# Driver.net
KiCad netlist of a schematic drawn in EAGLE
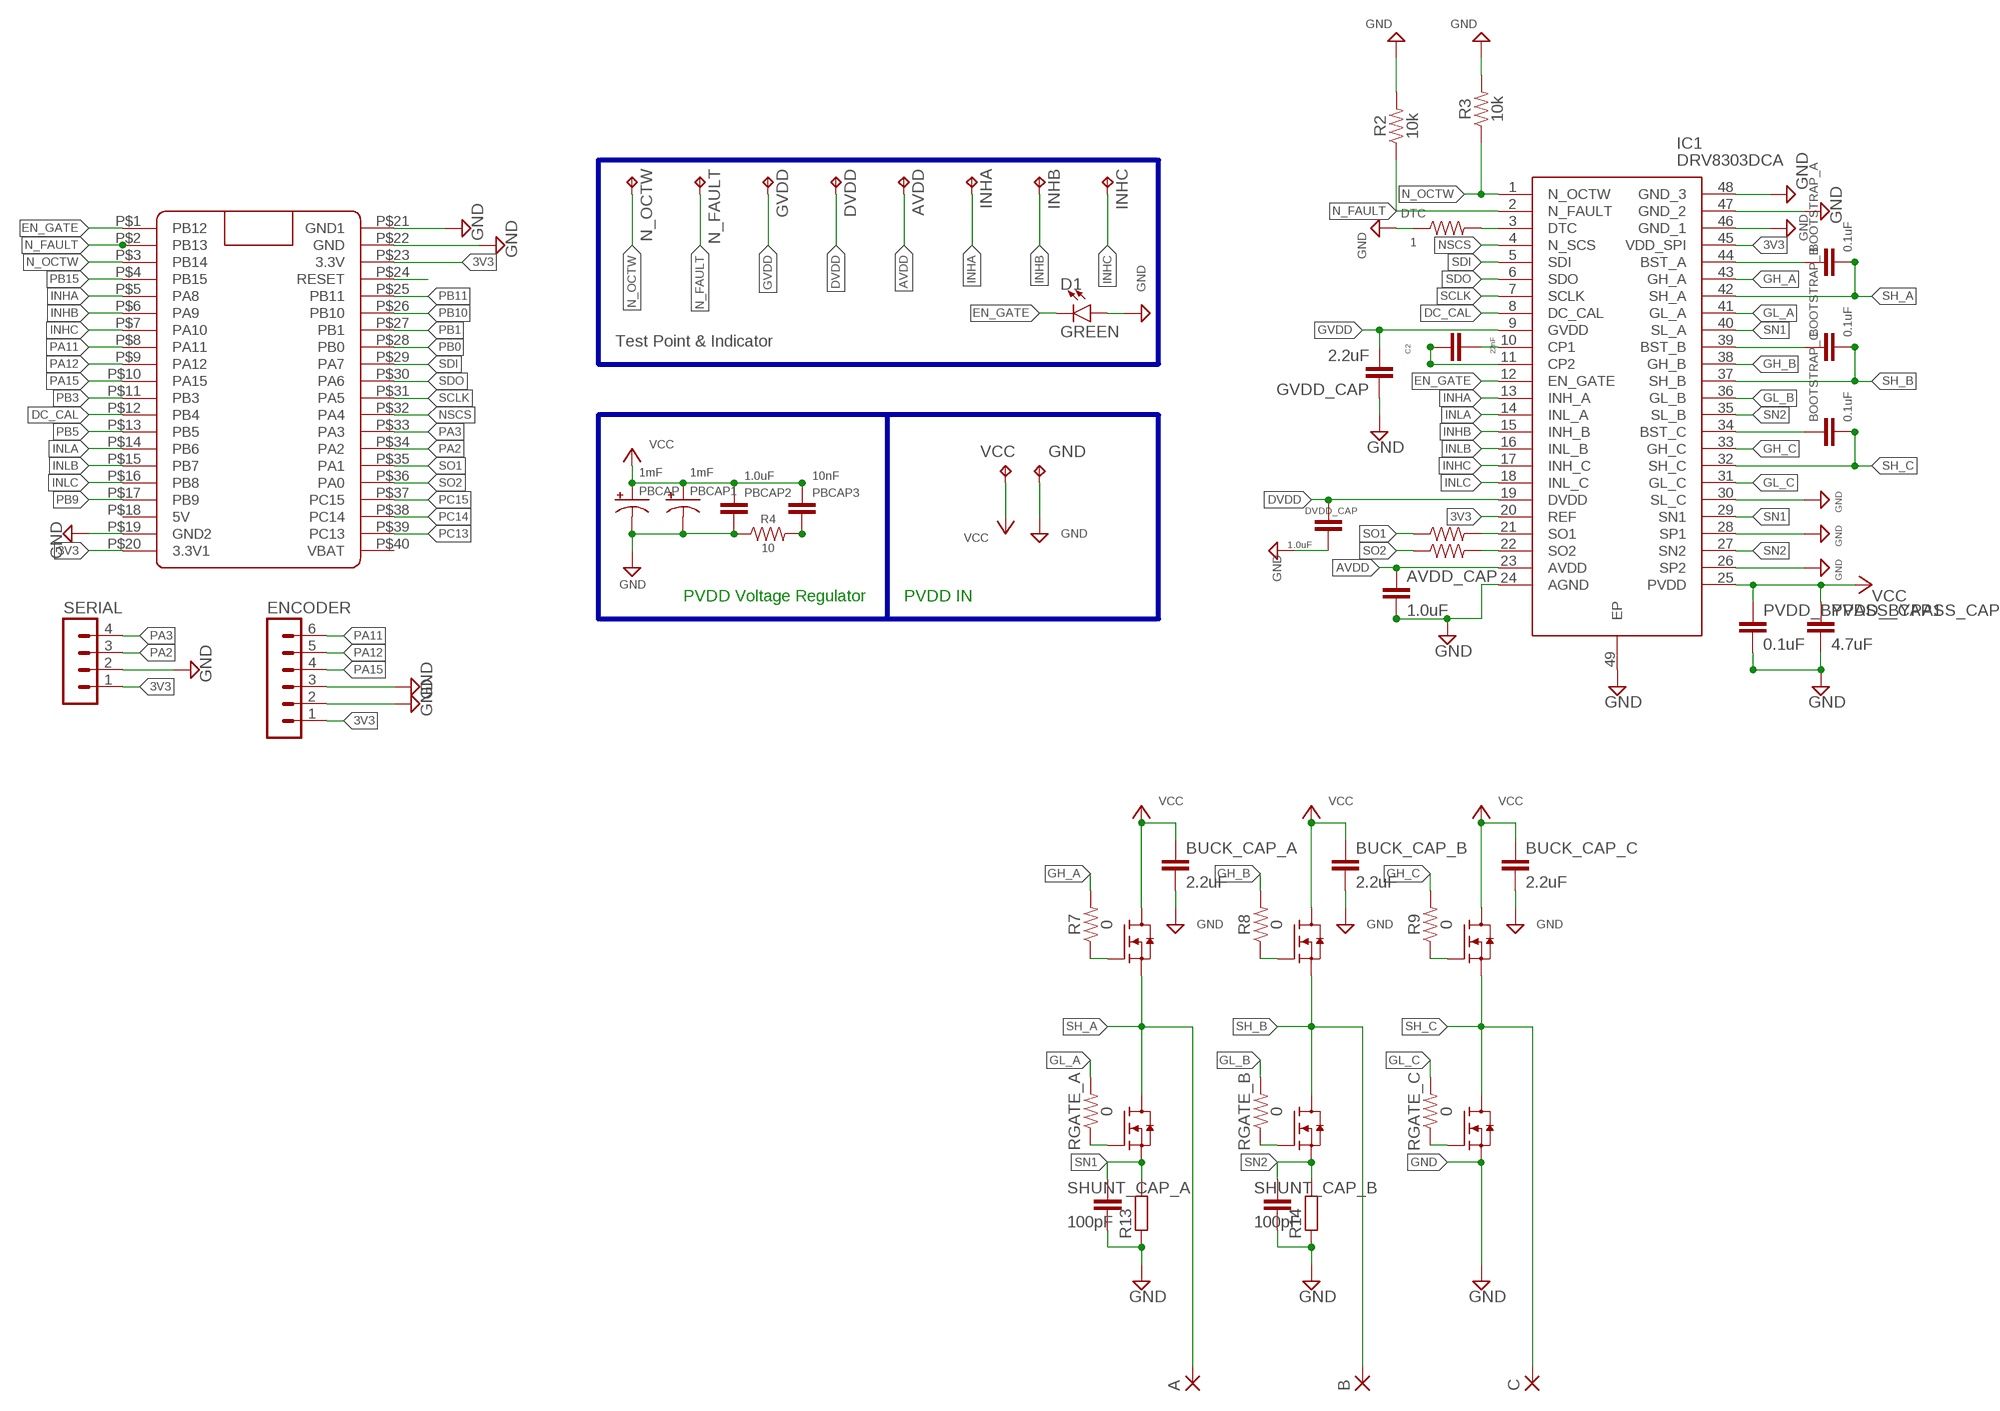
[diagram p0: schematic, sheet 1]

(export (version "E")
  (design (tool "Eeschema 10.0.6"))
  (components
    (comp (ref "A")
      (value "SMD5")
      (footprint "eagle-import:SMD2,54-5,08")
      (libsource (lib "eagle-import") (part "SMD5"))
    )
    (comp (ref "AVDD")
      (value "TPTP16R")
      (footprint "eagle-import:TP16R")
      (libsource (lib "eagle-import") (part "TPTP16R"))
    )
    (comp (ref "AVDD_CAP")
      (value "1.0uF")
      (footprint "eagle-import:0603")
      (libsource (lib "eagle-import") (part "1.0UF-0603-16V-10%"))
    )
    (comp (ref "B")
      (value "SMD5")
      (footprint "eagle-import:SMD2,54-5,08")
      (libsource (lib "eagle-import") (part "SMD5"))
    )
    (comp (ref "BOOTSTRAP_A")
      (value "0.1uF")
      (footprint "eagle-import:0603")
      (libsource (lib "eagle-import") (part "0.1UF-0603-25V-(+80/-20%)"))
    )
    (comp (ref "BOOTSTRAP_B")
      (value "0.1uF")
      (footprint "eagle-import:0603")
      (libsource (lib "eagle-import") (part "0.1UF-0603-25V-(+80/-20%)"))
    )
    (comp (ref "BOOTSTRAP_C")
      (value "0.1uF")
      (footprint "eagle-import:0603")
      (libsource (lib "eagle-import") (part "0.1UF-0603-25V-(+80/-20%)"))
    )
    (comp (ref "BUCK_CAP_A")
      (value "2.2uF")
      (footprint "eagle-import:0603")
      (libsource (lib "eagle-import") (part "2.2UF-0603-10V-20%"))
    )
    (comp (ref "BUCK_CAP_B")
      (value "2.2uF")
      (footprint "eagle-import:0603")
      (libsource (lib "eagle-import") (part "2.2UF-0603-10V-20%"))
    )
    (comp (ref "BUCK_CAP_C")
      (value "2.2uF")
      (footprint "eagle-import:0603")
      (libsource (lib "eagle-import") (part "2.2UF-0603-10V-20%"))
    )
    (comp (ref "C")
      (value "SMD5")
      (footprint "eagle-import:SMD2,54-5,08")
      (libsource (lib "eagle-import") (part "SMD5"))
    )
    (comp (ref "C2")
      (value "22nF")
      (footprint "eagle-import:0603")
      (libsource (lib "eagle-import") (part "22NF/22,000PF-0603-50V-10%"))
    )
    (comp (ref "D1")
      (value "GREEN")
      (footprint "eagle-import:LED-0603")
      (libsource (lib "eagle-import") (part "LED-GREEN0603"))
    )
    (comp (ref "DTC")
      (value "1")
      (footprint "eagle-import:0603")
      (libsource (lib "eagle-import") (part "1OHM-0603-1/10W-1%"))
    )
    (comp (ref "DVDD")
      (value "TPTP16R")
      (footprint "eagle-import:TP16R")
      (libsource (lib "eagle-import") (part "TPTP16R"))
    )
    (comp (ref "DVDD_CAP")
      (value "1.0uF")
      (footprint "eagle-import:0603")
      (libsource (lib "eagle-import") (part "1.0UF-0603-16V-10%"))
    )
    (comp (ref "ENCODER")
      (value "MA06-1")
      (footprint "eagle-import:MA06-1")
      (libsource (lib "eagle-import") (part "MA06-1"))
    )
    (comp (ref "GND")
      (value "TPPAD1-20Y")
      (footprint "eagle-import:P1-20Y")
      (libsource (lib "eagle-import") (part "TPPAD1-20Y"))
    )
    (comp (ref "GVDD")
      (value "TPTP16R")
      (footprint "eagle-import:TP16R")
      (libsource (lib "eagle-import") (part "TPTP16R"))
    )
    (comp (ref "GVDD_CAP")
      (value "2.2uF")
      (footprint "eagle-import:0603")
      (libsource (lib "eagle-import") (part "2.2UF-0603-10V-20%"))
    )
    (comp (ref "HA")
      (value "IRLR7843")
      (footprint "eagle-import:TO252")
      (libsource (lib "eagle-import") (part "IRLR7843"))
    )
    (comp (ref "HB")
      (value "IRLR7843")
      (footprint "eagle-import:TO252")
      (libsource (lib "eagle-import") (part "IRLR7843"))
    )
    (comp (ref "HC")
      (value "IRLR7843")
      (footprint "eagle-import:TO252")
      (libsource (lib "eagle-import") (part "IRLR7843"))
    )
    (comp (ref "IC1")
      (value "DRV8303DCA")
      (footprint "eagle-import:SOP50P810X120-49N")
      (fields (field (name "MOUSER_PART_NUMBER") "595-DRV8303DCA"))
      (libsource (lib "eagle-import") (part "DRV8303DCA"))
    )
    (comp (ref "INHA")
      (value "TPTP16R")
      (footprint "eagle-import:TP16R")
      (libsource (lib "eagle-import") (part "TPTP16R"))
    )
    (comp (ref "INHB")
      (value "TPTP16R")
      (footprint "eagle-import:TP16R")
      (libsource (lib "eagle-import") (part "TPTP16R"))
    )
    (comp (ref "INHC")
      (value "TPTP16R")
      (footprint "eagle-import:TP16R")
      (libsource (lib "eagle-import") (part "TPTP16R"))
    )
    (comp (ref "LA")
      (value "IRLR7843")
      (footprint "eagle-import:TO252")
      (libsource (lib "eagle-import") (part "IRLR7843"))
    )
    (comp (ref "LB")
      (value "IRLR7843")
      (footprint "eagle-import:TO252")
      (libsource (lib "eagle-import") (part "IRLR7843"))
    )
    (comp (ref "LC")
      (value "IRLR7843")
      (footprint "eagle-import:TO252")
      (libsource (lib "eagle-import") (part "IRLR7843"))
    )
    (comp (ref "N_FAULT")
      (value "TPTP16R")
      (footprint "eagle-import:TP16R")
      (libsource (lib "eagle-import") (part "TPTP16R"))
    )
    (comp (ref "N_OCTW")
      (value "TPTP16R")
      (footprint "eagle-import:TP16R")
      (libsource (lib "eagle-import") (part "TPTP16R"))
    )
    (comp (ref "PBCAP")
      (value "1mF")
      (footprint "eagle-import:CPOL-RADIAL-5MM-10MM")
      (libsource (lib "eagle-import") (part "1000UF-RADIAL-5MM-25V-20%"))
    )
    (comp (ref "PBCAP1")
      (value "1mF")
      (footprint "eagle-import:CPOL-RADIAL-5MM-10MM")
      (libsource (lib "eagle-import") (part "1000UF-RADIAL-5MM-25V-20%"))
    )
    (comp (ref "PBCAP2")
      (value "1.0uF")
      (footprint "eagle-import:0603")
      (libsource (lib "eagle-import") (part "1.0UF-0603-16V-10%"))
    )
    (comp (ref "PBCAP3")
      (value "10nF")
      (footprint "eagle-import:0603")
      (libsource (lib "eagle-import") (part "10NF-0603-50V-10%"))
    )
    (comp (ref "PVDD_BYPASS_CAP1")
      (value "0.1uF")
      (footprint "eagle-import:0603")
      (libsource (lib "eagle-import") (part "0.1UF-0603-25V-(+80/-20%)"))
    )
    (comp (ref "PVDD_BYPASS_CAP2")
      (value "4.7uF")
      (footprint "eagle-import:0603")
      (libsource (lib "eagle-import") (part "4.7UF-0603-35V-(20%)"))
    )
    (comp (ref "R2")
      (value "10k")
      (footprint "eagle-import:0603")
      (libsource (lib "eagle-import") (part "10KOHM-0603-1/10W-1%"))
    )
    (comp (ref "R3")
      (value "10k")
      (footprint "eagle-import:0603")
      (libsource (lib "eagle-import") (part "10KOHM-0603-1/10W-1%"))
    )
    (comp (ref "R4")
      (value "10")
      (footprint "eagle-import:0603")
      (libsource (lib "eagle-import") (part "10OHM-0603-1/10W-1%"))
    )
    (comp (ref "R5")
      (value "47")
      (footprint "eagle-import:0603")
      (libsource (lib "eagle-import") (part "47OHM-0603-1/10W-1%"))
    )
    (comp (ref "R6")
      (value "47")
      (footprint "eagle-import:0603")
      (libsource (lib "eagle-import") (part "47OHM-0603-1/10W-1%"))
    )
    (comp (ref "R7")
      (value "0")
      (footprint "eagle-import:0603")
      (libsource (lib "eagle-import") (part "0OHM-0603-1/10W"))
    )
    (comp (ref "R8")
      (value "0")
      (footprint "eagle-import:0603")
      (libsource (lib "eagle-import") (part "0OHM-0603-1/10W"))
    )
    (comp (ref "R9")
      (value "0")
      (footprint "eagle-import:0603")
      (libsource (lib "eagle-import") (part "0OHM-0603-1/10W"))
    )
    (comp (ref "R13")
      (value "R-EU_R2512")
      (footprint "eagle-import:R2512")
      (libsource (lib "eagle-import") (part "R-EU_R2512"))
    )
    (comp (ref "R14")
      (value "R-EU_R2512")
      (footprint "eagle-import:R2512")
      (libsource (lib "eagle-import") (part "R-EU_R2512"))
    )
    (comp (ref "RGATE_A")
      (value "0")
      (footprint "eagle-import:0603")
      (libsource (lib "eagle-import") (part "0OHM-0603-1/10W"))
    )
    (comp (ref "RGATE_B")
      (value "0")
      (footprint "eagle-import:0603")
      (libsource (lib "eagle-import") (part "0OHM-0603-1/10W"))
    )
    (comp (ref "RGATE_C")
      (value "0")
      (footprint "eagle-import:0603")
      (libsource (lib "eagle-import") (part "0OHM-0603-1/10W"))
    )
    (comp (ref "SERIAL")
      (value "MA04-1")
      (footprint "eagle-import:MA04-1")
      (libsource (lib "eagle-import") (part "MA04-1"))
    )
    (comp (ref "SHUNT_CAP_A")
      (value "100pF")
      (footprint "eagle-import:0603")
      (libsource (lib "eagle-import") (part "100PF-0603-50V-5%"))
    )
    (comp (ref "SHUNT_CAP_B")
      (value "100pF")
      (footprint "eagle-import:0603")
      (libsource (lib "eagle-import") (part "100PF-0603-50V-5%"))
    )
    (comp (ref "U$1")
      (value "BLUE_PILLADVANCED")
      (footprint "eagle-import:BLUE_PILL_ADV")
      (libsource (lib "eagle-import") (part "BLUE_PILLADVANCED"))
    )
    (comp (ref "VCC")
      (value "TPPAD1-20Y")
      (footprint "eagle-import:P1-20Y")
      (libsource (lib "eagle-import") (part "TPPAD1-20Y"))
    )
  )
  (nets
    (net (code "1") (name "3V3") (class "Default")
      (node (ref "ENCODER") (pin "1") (pinfunction "1_1") (pintype "passive"))
      (node (ref "IC1") (pin "20") (pinfunction "REF_20") (pintype "input"))
      (node (ref "IC1") (pin "45") (pinfunction "VDD_SPI_45") (pintype "power_in"))
      (node (ref "SERIAL") (pin "1") (pinfunction "1_1") (pintype "passive"))
      (node (ref "U$1") (pin "P$20") (pinfunction "3.3V1_P$20") (pintype "bidirectional"))
      (node (ref "U$1") (pin "P$23") (pinfunction "3.3V_P$23") (pintype "bidirectional"))
    )
    (net (code "2") (name "AVDD") (class "Default")
      (node (ref "AVDD") (pin "TP") (pinfunction "TP_TP") (pintype "input"))
      (node (ref "AVDD_CAP") (pin "1") (pinfunction "1_1") (pintype "passive"))
      (node (ref "IC1") (pin "23") (pinfunction "AVDD_23") (pintype "power_in"))
    )
    (net (code "3") (name "DC_CAL") (class "Default")
      (node (ref "IC1") (pin "8") (pinfunction "DC_CAL_8") (pintype "input"))
      (node (ref "U$1") (pin "P$12") (pinfunction "PB4_P$12") (pintype "bidirectional"))
    )
    (net (code "4") (name "DVDD") (class "Default")
      (node (ref "DVDD") (pin "TP") (pinfunction "TP_TP") (pintype "input"))
      (node (ref "DVDD_CAP") (pin "1") (pinfunction "1_1") (pintype "passive"))
      (node (ref "IC1") (pin "19") (pinfunction "DVDD_19") (pintype "power_in"))
    )
    (net (code "5") (name "EN_GATE") (class "Default")
      (node (ref "D1") (pin "C") (pinfunction "C_C") (pintype "passive"))
      (node (ref "IC1") (pin "12") (pinfunction "EN_GATE_12") (pintype "input"))
      (node (ref "U$1") (pin "P$1") (pinfunction "PB12_P$1") (pintype "bidirectional"))
    )
    (net (code "6") (name "GH_A") (class "Default")
      (node (ref "IC1") (pin "43") (pinfunction "GH_A_43") (pintype "output"))
      (node (ref "R7") (pin "2") (pinfunction "2_2") (pintype "passive"))
    )
    (net (code "7") (name "GH_B") (class "Default")
      (node (ref "IC1") (pin "38") (pinfunction "GH_B_38") (pintype "output"))
      (node (ref "R8") (pin "2") (pinfunction "2_2") (pintype "passive"))
    )
    (net (code "8") (name "GH_C") (class "Default")
      (node (ref "IC1") (pin "33") (pinfunction "GH_C_33") (pintype "output"))
      (node (ref "R9") (pin "2") (pinfunction "2_2") (pintype "passive"))
    )
    (net (code "9") (name "GL_A") (class "Default")
      (node (ref "IC1") (pin "41") (pinfunction "GL_A_41") (pintype "output"))
      (node (ref "RGATE_A") (pin "2") (pinfunction "2_2") (pintype "passive"))
    )
    (net (code "10") (name "GL_B") (class "Default")
      (node (ref "IC1") (pin "36") (pinfunction "GL_B_36") (pintype "output"))
      (node (ref "RGATE_B") (pin "2") (pinfunction "2_2") (pintype "passive"))
    )
    (net (code "11") (name "GL_C") (class "Default")
      (node (ref "IC1") (pin "31") (pinfunction "GL_C_31") (pintype "output"))
      (node (ref "RGATE_C") (pin "2") (pinfunction "2_2") (pintype "passive"))
    )
    (net (code "12") (name "GND") (class "Default")
      (node (ref "AVDD_CAP") (pin "2") (pinfunction "2_2") (pintype "passive"))
      (node (ref "BUCK_CAP_A") (pin "2") (pinfunction "2_2") (pintype "passive"))
      (node (ref "BUCK_CAP_B") (pin "2") (pinfunction "2_2") (pintype "passive"))
      (node (ref "BUCK_CAP_C") (pin "2") (pinfunction "2_2") (pintype "passive"))
      (node (ref "D1") (pin "A") (pinfunction "A_A") (pintype "passive"))
      (node (ref "DTC") (pin "1") (pinfunction "1_1") (pintype "passive"))
      (node (ref "DVDD_CAP") (pin "2") (pinfunction "2_2") (pintype "passive"))
      (node (ref "ENCODER") (pin "2") (pinfunction "2_2") (pintype "passive"))
      (node (ref "ENCODER") (pin "3") (pinfunction "3_3") (pintype "passive"))
      (node (ref "GND") (pin "TP") (pinfunction "TP_TP") (pintype "input"))
      (node (ref "GVDD_CAP") (pin "1") (pinfunction "1_1") (pintype "passive"))
      (node (ref "IC1") (pin "24") (pinfunction "AGND_24") (pintype "power_in"))
      (node (ref "IC1") (pin "26") (pinfunction "SP2_26") (pintype "input"))
      (node (ref "IC1") (pin "28") (pinfunction "SP1_28") (pintype "input"))
      (node (ref "IC1") (pin "30") (pinfunction "SL_C_30") (pintype "input"))
      (node (ref "IC1") (pin "46") (pinfunction "GND_1_46") (pintype "power_in"))
      (node (ref "IC1") (pin "47") (pinfunction "GND_2_47") (pintype "power_in"))
      (node (ref "IC1") (pin "48") (pinfunction "GND_3_48") (pintype "power_in"))
      (node (ref "IC1") (pin "49") (pinfunction "EP_49") (pintype "bidirectional"))
      (node (ref "LC") (pin "2") (pinfunction "S_2") (pintype "passive"))
      (node (ref "PBCAP") (pin "-") (pinfunction "-_-") (pintype "passive"))
      (node (ref "PBCAP1") (pin "-") (pinfunction "-_-") (pintype "passive"))
      (node (ref "PBCAP2") (pin "2") (pinfunction "2_2") (pintype "passive"))
      (node (ref "PVDD_BYPASS_CAP1") (pin "2") (pinfunction "2_2") (pintype "passive"))
      (node (ref "PVDD_BYPASS_CAP2") (pin "2") (pinfunction "2_2") (pintype "passive"))
      (node (ref "R13") (pin "1") (pinfunction "1_1") (pintype "passive"))
      (node (ref "R14") (pin "1") (pinfunction "1_1") (pintype "passive"))
      (node (ref "R2") (pin "2") (pinfunction "2_2") (pintype "passive"))
      (node (ref "R3") (pin "2") (pinfunction "2_2") (pintype "passive"))
      (node (ref "R4") (pin "1") (pinfunction "1_1") (pintype "passive"))
      (node (ref "SERIAL") (pin "2") (pinfunction "2_2") (pintype "passive"))
      (node (ref "SHUNT_CAP_A") (pin "2") (pinfunction "2_2") (pintype "passive"))
      (node (ref "SHUNT_CAP_B") (pin "2") (pinfunction "2_2") (pintype "passive"))
      (node (ref "U$1") (pin "P$19") (pinfunction "GND2_P$19") (pintype "bidirectional"))
      (node (ref "U$1") (pin "P$21") (pinfunction "GND1_P$21") (pintype "power_in"))
      (node (ref "U$1") (pin "P$22") (pinfunction "GND_P$22") (pintype "bidirectional"))
    )
    (net (code "13") (name "GVDD") (class "Default")
      (node (ref "GVDD") (pin "TP") (pinfunction "TP_TP") (pintype "input"))
      (node (ref "GVDD_CAP") (pin "2") (pinfunction "2_2") (pintype "passive"))
      (node (ref "IC1") (pin "9") (pinfunction "GVDD_9") (pintype "power_in"))
    )
    (net (code "14") (name "INHA") (class "Default")
      (node (ref "IC1") (pin "13") (pinfunction "INH_A_13") (pintype "input"))
      (node (ref "INHA") (pin "TP") (pinfunction "TP_TP") (pintype "input"))
      (node (ref "U$1") (pin "P$5") (pinfunction "PA8_P$5") (pintype "bidirectional"))
    )
    (net (code "15") (name "INHB") (class "Default")
      (node (ref "IC1") (pin "15") (pinfunction "INH_B_15") (pintype "input"))
      (node (ref "INHB") (pin "TP") (pinfunction "TP_TP") (pintype "input"))
      (node (ref "U$1") (pin "P$6") (pinfunction "PA9_P$6") (pintype "bidirectional"))
    )
    (net (code "16") (name "INHC") (class "Default")
      (node (ref "IC1") (pin "17") (pinfunction "INH_C_17") (pintype "input"))
      (node (ref "INHC") (pin "TP") (pinfunction "TP_TP") (pintype "input"))
      (node (ref "U$1") (pin "P$7") (pinfunction "PA10_P$7") (pintype "bidirectional"))
    )
    (net (code "17") (name "INLA") (class "Default")
      (node (ref "IC1") (pin "14") (pinfunction "INL_A_14") (pintype "input"))
      (node (ref "U$1") (pin "P$14") (pinfunction "PB6_P$14") (pintype "bidirectional"))
    )
    (net (code "18") (name "INLB") (class "Default")
      (node (ref "IC1") (pin "16") (pinfunction "INL_B_16") (pintype "input"))
      (node (ref "U$1") (pin "P$15") (pinfunction "PB7_P$15") (pintype "bidirectional"))
    )
    (net (code "19") (name "INLC") (class "Default")
      (node (ref "IC1") (pin "18") (pinfunction "INL_C_18") (pintype "input"))
      (node (ref "U$1") (pin "P$16") (pinfunction "PB8_P$16") (pintype "bidirectional"))
    )
    (net (code "20") (name "NSCS") (class "Default")
      (node (ref "IC1") (pin "4") (pinfunction "N_SCS_4") (pintype "input"))
      (node (ref "U$1") (pin "P$32") (pinfunction "PA4_P$32") (pintype "bidirectional"))
    )
    (net (code "21") (name "N_FAULT") (class "Default")
      (node (ref "IC1") (pin "2") (pinfunction "N_FAULT_2") (pintype "output"))
      (node (ref "N_FAULT") (pin "TP") (pinfunction "TP_TP") (pintype "input"))
      (node (ref "R2") (pin "1") (pinfunction "1_1") (pintype "passive"))
      (node (ref "U$1") (pin "P$2") (pinfunction "PB13_P$2") (pintype "bidirectional"))
    )
    (net (code "22") (name "N_OCTW") (class "Default")
      (node (ref "IC1") (pin "1") (pinfunction "N_OCTW_1") (pintype "output"))
      (node (ref "N_OCTW") (pin "TP") (pinfunction "TP_TP") (pintype "input"))
      (node (ref "R3") (pin "1") (pinfunction "1_1") (pintype "passive"))
      (node (ref "U$1") (pin "P$3") (pinfunction "PB14_P$3") (pintype "bidirectional"))
    )
    (net (code "23") (name "Net-(HA-G)") (class "Default")
      (node (ref "HA") (pin "1") (pinfunction "G_1") (pintype "passive"))
      (node (ref "R7") (pin "1") (pinfunction "1_1") (pintype "passive"))
    )
    (net (code "24") (name "Net-(HB-G)") (class "Default")
      (node (ref "HB") (pin "1") (pinfunction "G_1") (pintype "passive"))
      (node (ref "R8") (pin "1") (pinfunction "1_1") (pintype "passive"))
    )
    (net (code "25") (name "Net-(HC-G)") (class "Default")
      (node (ref "HC") (pin "1") (pinfunction "G_1") (pintype "passive"))
      (node (ref "R9") (pin "1") (pinfunction "1_1") (pintype "passive"))
    )
    (net (code "26") (name "Net-(IC1-BST_A)") (class "Default")
      (node (ref "BOOTSTRAP_A") (pin "1") (pinfunction "1_1") (pintype "passive"))
      (node (ref "IC1") (pin "44") (pinfunction "BST_A_44") (pintype "bidirectional"))
    )
    (net (code "27") (name "Net-(IC1-BST_B)") (class "Default")
      (node (ref "BOOTSTRAP_B") (pin "1") (pinfunction "1_1") (pintype "passive"))
      (node (ref "IC1") (pin "39") (pinfunction "BST_B_39") (pintype "bidirectional"))
    )
    (net (code "28") (name "Net-(IC1-BST_C)") (class "Default")
      (node (ref "BOOTSTRAP_C") (pin "1") (pinfunction "1_1") (pintype "passive"))
      (node (ref "IC1") (pin "34") (pinfunction "BST_C_34") (pintype "bidirectional"))
    )
    (net (code "29") (name "Net-(IC1-CP1)") (class "Default")
      (node (ref "C2") (pin "2") (pinfunction "2_2") (pintype "passive"))
      (node (ref "IC1") (pin "10") (pinfunction "CP1_10") (pintype "power_in"))
    )
    (net (code "30") (name "Net-(IC1-CP2)") (class "Default")
      (node (ref "C2") (pin "1") (pinfunction "1_1") (pintype "passive"))
      (node (ref "IC1") (pin "11") (pinfunction "CP2_11") (pintype "power_in"))
    )
    (net (code "31") (name "Net-(IC1-DTC)") (class "Default")
      (node (ref "DTC") (pin "2") (pinfunction "2_2") (pintype "passive"))
      (node (ref "IC1") (pin "3") (pinfunction "DTC_3") (pintype "input"))
    )
    (net (code "32") (name "Net-(IC1-SO1)") (class "Default")
      (node (ref "IC1") (pin "21") (pinfunction "SO1_21") (pintype "output"))
      (node (ref "R5") (pin "2") (pinfunction "2_2") (pintype "passive"))
    )
    (net (code "33") (name "Net-(IC1-SO2)") (class "Default")
      (node (ref "IC1") (pin "22") (pinfunction "SO2_22") (pintype "output"))
      (node (ref "R6") (pin "2") (pinfunction "2_2") (pintype "passive"))
    )
    (net (code "34") (name "Net-(LA-G)") (class "Default")
      (node (ref "LA") (pin "1") (pinfunction "G_1") (pintype "passive"))
      (node (ref "RGATE_A") (pin "1") (pinfunction "1_1") (pintype "passive"))
    )
    (net (code "35") (name "Net-(LB-G)") (class "Default")
      (node (ref "LB") (pin "1") (pinfunction "G_1") (pintype "passive"))
      (node (ref "RGATE_B") (pin "1") (pinfunction "1_1") (pintype "passive"))
    )
    (net (code "36") (name "Net-(LC-G)") (class "Default")
      (node (ref "LC") (pin "1") (pinfunction "G_1") (pintype "passive"))
      (node (ref "RGATE_C") (pin "1") (pinfunction "1_1") (pintype "passive"))
    )
    (net (code "37") (name "Net-(PBCAP3-Pad2)") (class "Default")
      (node (ref "PBCAP3") (pin "2") (pinfunction "2_2") (pintype "passive"))
      (node (ref "R4") (pin "2") (pinfunction "2_2") (pintype "passive"))
    )
    (net (code "38") (name "PA2") (class "Default")
      (node (ref "SERIAL") (pin "3") (pinfunction "3_3") (pintype "passive"))
      (node (ref "U$1") (pin "P$34") (pinfunction "PA2_P$34") (pintype "bidirectional"))
    )
    (net (code "39") (name "PA3") (class "Default")
      (node (ref "SERIAL") (pin "4") (pinfunction "4_4") (pintype "passive"))
      (node (ref "U$1") (pin "P$33") (pinfunction "PA3_P$33") (pintype "bidirectional"))
    )
    (net (code "40") (name "PA11") (class "Default")
      (node (ref "ENCODER") (pin "6") (pinfunction "6_6") (pintype "passive"))
      (node (ref "U$1") (pin "P$8") (pinfunction "PA11_P$8") (pintype "bidirectional"))
    )
    (net (code "41") (name "PA12") (class "Default")
      (node (ref "ENCODER") (pin "5") (pinfunction "5_5") (pintype "passive"))
      (node (ref "U$1") (pin "P$9") (pinfunction "PA12_P$9") (pintype "bidirectional"))
    )
    (net (code "42") (name "PA15") (class "Default")
      (node (ref "ENCODER") (pin "4") (pinfunction "4_4") (pintype "passive"))
      (node (ref "U$1") (pin "P$10") (pinfunction "PA15_P$10") (pintype "bidirectional"))
    )
    (net (code "43") (name "PB0") (class "Default")
      (node (ref "U$1") (pin "P$28") (pinfunction "PB0_P$28") (pintype "bidirectional"))
    )
    (net (code "44") (name "PB1") (class "Default")
      (node (ref "U$1") (pin "P$27") (pinfunction "PB1_P$27") (pintype "bidirectional"))
    )
    (net (code "45") (name "PB3") (class "Default")
      (node (ref "U$1") (pin "P$11") (pinfunction "PB3_P$11") (pintype "bidirectional"))
    )
    (net (code "46") (name "PB5") (class "Default")
      (node (ref "U$1") (pin "P$13") (pinfunction "PB5_P$13") (pintype "bidirectional"))
    )
    (net (code "47") (name "PB9") (class "Default")
      (node (ref "U$1") (pin "P$17") (pinfunction "PB9_P$17") (pintype "bidirectional"))
    )
    (net (code "48") (name "PB10") (class "Default")
      (node (ref "U$1") (pin "P$26") (pinfunction "PB10_P$26") (pintype "bidirectional"))
    )
    (net (code "49") (name "PB11") (class "Default")
      (node (ref "U$1") (pin "P$25") (pinfunction "PB11_P$25") (pintype "bidirectional"))
    )
    (net (code "50") (name "PB15") (class "Default")
      (node (ref "U$1") (pin "P$4") (pinfunction "PB15_P$4") (pintype "bidirectional"))
    )
    (net (code "51") (name "PC13") (class "Default")
      (node (ref "U$1") (pin "P$39") (pinfunction "PC13_P$39") (pintype "bidirectional"))
    )
    (net (code "52") (name "PC14") (class "Default")
      (node (ref "U$1") (pin "P$38") (pinfunction "PC14_P$38") (pintype "bidirectional"))
    )
    (net (code "53") (name "PC15") (class "Default")
      (node (ref "U$1") (pin "P$37") (pinfunction "PC15_P$37") (pintype "bidirectional"))
    )
    (net (code "54") (name "SCLK") (class "Default")
      (node (ref "IC1") (pin "7") (pinfunction "SCLK_7") (pintype "input"))
      (node (ref "U$1") (pin "P$31") (pinfunction "PA5_P$31") (pintype "bidirectional"))
    )
    (net (code "55") (name "SDI") (class "Default")
      (node (ref "IC1") (pin "5") (pinfunction "SDI_5") (pintype "input"))
      (node (ref "U$1") (pin "P$29") (pinfunction "PA7_P$29") (pintype "bidirectional"))
    )
    (net (code "56") (name "SDO") (class "Default")
      (node (ref "IC1") (pin "6") (pinfunction "SDO_6") (pintype "output"))
      (node (ref "U$1") (pin "P$30") (pinfunction "PA6_P$30") (pintype "bidirectional"))
    )
    (net (code "57") (name "SH_A") (class "Default")
      (node (ref "A") (pin "1") (pinfunction "P_1") (pintype "passive"))
      (node (ref "BOOTSTRAP_A") (pin "2") (pinfunction "2_2") (pintype "passive"))
      (node (ref "HA") (pin "2") (pinfunction "S_2") (pintype "passive"))
      (node (ref "IC1") (pin "42") (pinfunction "SH_A_42") (pintype "input"))
      (node (ref "LA") (pin "3") (pinfunction "D_3") (pintype "passive"))
    )
    (net (code "58") (name "SH_B") (class "Default")
      (node (ref "B") (pin "1") (pinfunction "P_1") (pintype "passive"))
      (node (ref "BOOTSTRAP_B") (pin "2") (pinfunction "2_2") (pintype "passive"))
      (node (ref "HB") (pin "2") (pinfunction "S_2") (pintype "passive"))
      (node (ref "IC1") (pin "37") (pinfunction "SH_B_37") (pintype "input"))
      (node (ref "LB") (pin "3") (pinfunction "D_3") (pintype "passive"))
    )
    (net (code "59") (name "SH_C") (class "Default")
      (node (ref "BOOTSTRAP_C") (pin "2") (pinfunction "2_2") (pintype "passive"))
      (node (ref "C") (pin "1") (pinfunction "P_1") (pintype "passive"))
      (node (ref "HC") (pin "2") (pinfunction "S_2") (pintype "passive"))
      (node (ref "IC1") (pin "32") (pinfunction "SH_C_32") (pintype "input"))
      (node (ref "LC") (pin "3") (pinfunction "D_3") (pintype "passive"))
    )
    (net (code "60") (name "SN1") (class "Default")
      (node (ref "IC1") (pin "29") (pinfunction "SN1_29") (pintype "input"))
      (node (ref "IC1") (pin "40") (pinfunction "SL_A_40") (pintype "input"))
      (node (ref "LA") (pin "2") (pinfunction "S_2") (pintype "passive"))
      (node (ref "R13") (pin "2") (pinfunction "2_2") (pintype "passive"))
      (node (ref "SHUNT_CAP_A") (pin "1") (pinfunction "1_1") (pintype "passive"))
    )
    (net (code "61") (name "SN2") (class "Default")
      (node (ref "IC1") (pin "27") (pinfunction "SN2_27") (pintype "input"))
      (node (ref "IC1") (pin "35") (pinfunction "SL_B_35") (pintype "input"))
      (node (ref "LB") (pin "2") (pinfunction "S_2") (pintype "passive"))
      (node (ref "R14") (pin "2") (pinfunction "2_2") (pintype "passive"))
      (node (ref "SHUNT_CAP_B") (pin "1") (pinfunction "1_1") (pintype "passive"))
    )
    (net (code "62") (name "SO1") (class "Default")
      (node (ref "R5") (pin "1") (pinfunction "1_1") (pintype "passive"))
      (node (ref "U$1") (pin "P$35") (pinfunction "PA1_P$35") (pintype "bidirectional"))
    )
    (net (code "63") (name "SO2") (class "Default")
      (node (ref "R6") (pin "1") (pinfunction "1_1") (pintype "passive"))
      (node (ref "U$1") (pin "P$36") (pinfunction "PA0_P$36") (pintype "bidirectional"))
    )
    (net (code "64") (name "VCC") (class "Default")
      (node (ref "BUCK_CAP_A") (pin "1") (pinfunction "1_1") (pintype "passive"))
      (node (ref "BUCK_CAP_B") (pin "1") (pinfunction "1_1") (pintype "passive"))
      (node (ref "BUCK_CAP_C") (pin "1") (pinfunction "1_1") (pintype "passive"))
      (node (ref "HA") (pin "3") (pinfunction "D_3") (pintype "passive"))
      (node (ref "HB") (pin "3") (pinfunction "D_3") (pintype "passive"))
      (node (ref "HC") (pin "3") (pinfunction "D_3") (pintype "passive"))
      (node (ref "IC1") (pin "25") (pinfunction "PVDD_25") (pintype "power_in"))
      (node (ref "PBCAP") (pin "+") (pinfunction "+_+") (pintype "passive"))
      (node (ref "PBCAP1") (pin "+") (pinfunction "+_+") (pintype "passive"))
      (node (ref "PBCAP2") (pin "1") (pinfunction "1_1") (pintype "passive"))
      (node (ref "PBCAP3") (pin "1") (pinfunction "1_1") (pintype "passive"))
      (node (ref "PVDD_BYPASS_CAP1") (pin "1") (pinfunction "1_1") (pintype "passive"))
      (node (ref "PVDD_BYPASS_CAP2") (pin "1") (pinfunction "1_1") (pintype "passive"))
      (node (ref "VCC") (pin "TP") (pinfunction "TP_TP") (pintype "input"))
    )
    (net (code "65") (name "unconnected-(U$1-5V-PadP$18)") (class "Default")
      (node (ref "U$1") (pin "P$18") (pinfunction "5V_P$18") (pintype "bidirectional"))
    )
    (net (code "66") (name "unconnected-(U$1-RESET-PadP$24)") (class "Default")
      (node (ref "U$1") (pin "P$24") (pinfunction "RESET_P$24") (pintype "bidirectional"))
    )
    (net (code "67") (name "unconnected-(U$1-VBAT-PadP$40)") (class "Default")
      (node (ref "U$1") (pin "P$40") (pinfunction "VBAT_P$40") (pintype "bidirectional"))
    )
  )
)
